# ADC_8681.net
KiCad netlist of a schematic drawn in Altium Designer
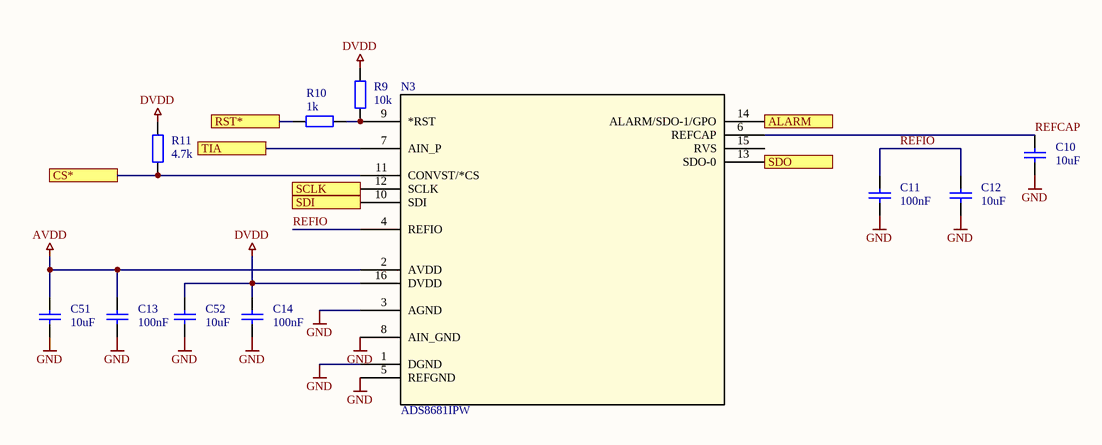
[diagram p0: ADC_8681.SchDoc]

(export (version "E")
  (design (tool "Eeschema 10.0.6"))
  (components
    (comp (ref "C10")
      (value "10uF")
      (footprint "C1206-KUE")
      (description "Capacitor")
      (fields (field (name "MANUFACTURER") "Kemet") (field (name "PUBLISHER") "Altium Limited"))
      (libsource (lib "ExtrapartsKUE_V01") (part "Capacitor"))
    )
    (comp (ref "C11")
      (value "100nF")
      (footprint "C1206-KUE")
      (description "Capacitor")
      (fields (field (name "MANUFACTURER") "Kemet") (field (name "PUBLISHER") "Altium Limited"))
      (libsource (lib "ExtrapartsKUE_V01") (part "Capacitor"))
    )
    (comp (ref "C12")
      (value "10uF")
      (footprint "C1206-KUE")
      (description "Capacitor")
      (fields (field (name "MANUFACTURER") "Kemet") (field (name "PUBLISHER") "Altium Limited"))
      (libsource (lib "ExtrapartsKUE_V01") (part "Capacitor"))
    )
    (comp (ref "C13")
      (value "100nF")
      (footprint "C1206-KUE")
      (description "Capacitor")
      (fields (field (name "MANUFACTURER") "Kemet") (field (name "PUBLISHER") "Altium Limited"))
      (libsource (lib "ExtrapartsKUE_V01") (part "Capacitor"))
    )
    (comp (ref "C14")
      (value "100nF")
      (footprint "C1206-KUE")
      (description "Capacitor")
      (fields (field (name "MANUFACTURER") "Kemet") (field (name "PUBLISHER") "Altium Limited"))
      (libsource (lib "ExtrapartsKUE_V01") (part "Capacitor"))
    )
    (comp (ref "C51")
      (value "10uF")
      (footprint "C1206-KUE")
      (description "Capacitor")
      (fields (field (name "MANUFACTURER") "Kemet") (field (name "PUBLISHER") "Altium Limited"))
      (libsource (lib "ExtrapartsKUE_V01") (part "Capacitor"))
    )
    (comp (ref "C52")
      (value "10uF")
      (footprint "C1206-KUE")
      (description "Capacitor")
      (fields (field (name "MANUFACTURER") "Kemet") (field (name "PUBLISHER") "Altium Limited"))
      (libsource (lib "ExtrapartsKUE_V01") (part "Capacitor"))
    )
    (comp (ref "N3")
      (value "ADS8681IPW")
      (footprint "PW16_TEX")
      (fields (field (name "COPYRIGHT") "Copyright (C) 2025 Ultra Librarian. All rights reserved."))
      (libsource (lib "ADS8681IPW") (part "ADS8681IPW"))
    )
    (comp (ref "R9")
      (value "10k")
      (footprint "C1206-KUE")
      (description "Resistor SMD")
      (fields (field (name "MANUFACTURER") "AVX") (field (name "PUBLISHER") "Altium Limited"))
      (libsource (lib "ExtrapartsKUE_V01") (part "ResistorSMD"))
    )
    (comp (ref "R10")
      (value "1k")
      (footprint "C1206-KUE")
      (description "Resistor SMD")
      (fields (field (name "MANUFACTURER") "AVX") (field (name "PUBLISHER") "Altium Limited"))
      (libsource (lib "") (part "ResistorSMD_1"))
    )
    (comp (ref "R11")
      (value "4.7k")
      (footprint "C1206-KUE")
      (description "Resistor SMD")
      (fields (field (name "MANUFACTURER") "AVX") (field (name "PUBLISHER") "Altium Limited"))
      (libsource (lib "ExtrapartsKUE_V01") (part "ResistorSMD"))
    )
  )
  (nets
    (net (code "1") (name "/ALARM") (class "Default")
      (node (ref "N3") (pin "14") (pinfunction "ALARM/SDO-1/GPO_14") (pintype "passive"))
    )
    (net (code "2") (name "/CS*") (class "Default")
      (node (ref "N3") (pin "11") (pinfunction "CONVST/*CS_11") (pintype "passive"))
      (node (ref "R11") (pin "2") (pinfunction "2_2") (pintype "passive"))
    )
    (net (code "3") (name "/REFCAP") (class "Default")
      (node (ref "C10") (pin "2") (pinfunction "2_2") (pintype "passive"))
      (node (ref "N3") (pin "6") (pinfunction "REFCAP_6") (pintype "passive"))
    )
    (net (code "4") (name "/REFIO") (class "Default")
      (node (ref "C11") (pin "2") (pinfunction "2_2") (pintype "passive"))
      (node (ref "C12") (pin "2") (pinfunction "2_2") (pintype "passive"))
      (node (ref "N3") (pin "4") (pinfunction "REFIO_4") (pintype "passive"))
    )
    (net (code "5") (name "/RST*") (class "Default")
      (node (ref "R10") (pin "1") (pinfunction "1_1") (pintype "passive"))
    )
    (net (code "6") (name "/SCLK") (class "Default")
      (node (ref "N3") (pin "12") (pinfunction "SCLK_12") (pintype "passive"))
    )
    (net (code "7") (name "/SDI") (class "Default")
      (node (ref "N3") (pin "10") (pinfunction "SDI_10") (pintype "passive"))
    )
    (net (code "8") (name "/SDO") (class "Default")
      (node (ref "N3") (pin "13") (pinfunction "SDO-0_13") (pintype "passive"))
    )
    (net (code "9") (name "/TIA") (class "Default")
      (node (ref "N3") (pin "7") (pinfunction "AIN_P_7") (pintype "passive"))
    )
    (net (code "10") (name "AVDD") (class "Default")
      (node (ref "C13") (pin "2") (pinfunction "2_2") (pintype "passive"))
      (node (ref "C51") (pin "2") (pinfunction "2_2") (pintype "passive"))
      (node (ref "N3") (pin "2") (pinfunction "AVDD_2") (pintype "power_in"))
    )
    (net (code "11") (name "DVDD") (class "Default")
      (node (ref "C14") (pin "2") (pinfunction "2_2") (pintype "passive"))
      (node (ref "C52") (pin "2") (pinfunction "2_2") (pintype "passive"))
      (node (ref "N3") (pin "16") (pinfunction "DVDD_16") (pintype "power_in"))
      (node (ref "R11") (pin "1") (pinfunction "1_1") (pintype "passive"))
      (node (ref "R9") (pin "1") (pinfunction "1_1") (pintype "passive"))
    )
    (net (code "12") (name "GND") (class "Default")
      (node (ref "C10") (pin "1") (pinfunction "1_1") (pintype "passive"))
      (node (ref "C11") (pin "1") (pinfunction "1_1") (pintype "passive"))
      (node (ref "C12") (pin "1") (pinfunction "1_1") (pintype "passive"))
      (node (ref "C13") (pin "1") (pinfunction "1_1") (pintype "passive"))
      (node (ref "C14") (pin "1") (pinfunction "1_1") (pintype "passive"))
      (node (ref "C51") (pin "1") (pinfunction "1_1") (pintype "passive"))
      (node (ref "C52") (pin "1") (pinfunction "1_1") (pintype "passive"))
      (node (ref "N3") (pin "1") (pinfunction "DGND_1") (pintype "power_in"))
      (node (ref "N3") (pin "3") (pinfunction "AGND_3") (pintype "power_in"))
      (node (ref "N3") (pin "5") (pinfunction "REFGND_5") (pintype "power_in"))
      (node (ref "N3") (pin "8") (pinfunction "AIN_GND_8") (pintype "passive"))
    )
    (net (code "13") (name "Net-(N3-*RST)") (class "Default")
      (node (ref "N3") (pin "9") (pinfunction "*RST_9") (pintype "passive"))
      (node (ref "R10") (pin "2") (pinfunction "2_2") (pintype "passive"))
      (node (ref "R9") (pin "2") (pinfunction "2_2") (pintype "passive"))
    )
    (net (code "14") (name "unconnected-(N3-RVS-Pad15)") (class "Default")
      (node (ref "N3") (pin "15") (pinfunction "RVS_15") (pintype "passive"))
    )
  )
)
